# EVB-ANNA-B5_SCHEM_0005_On-Board-Debug.net
KiCad netlist of a schematic drawn in Altium Designer
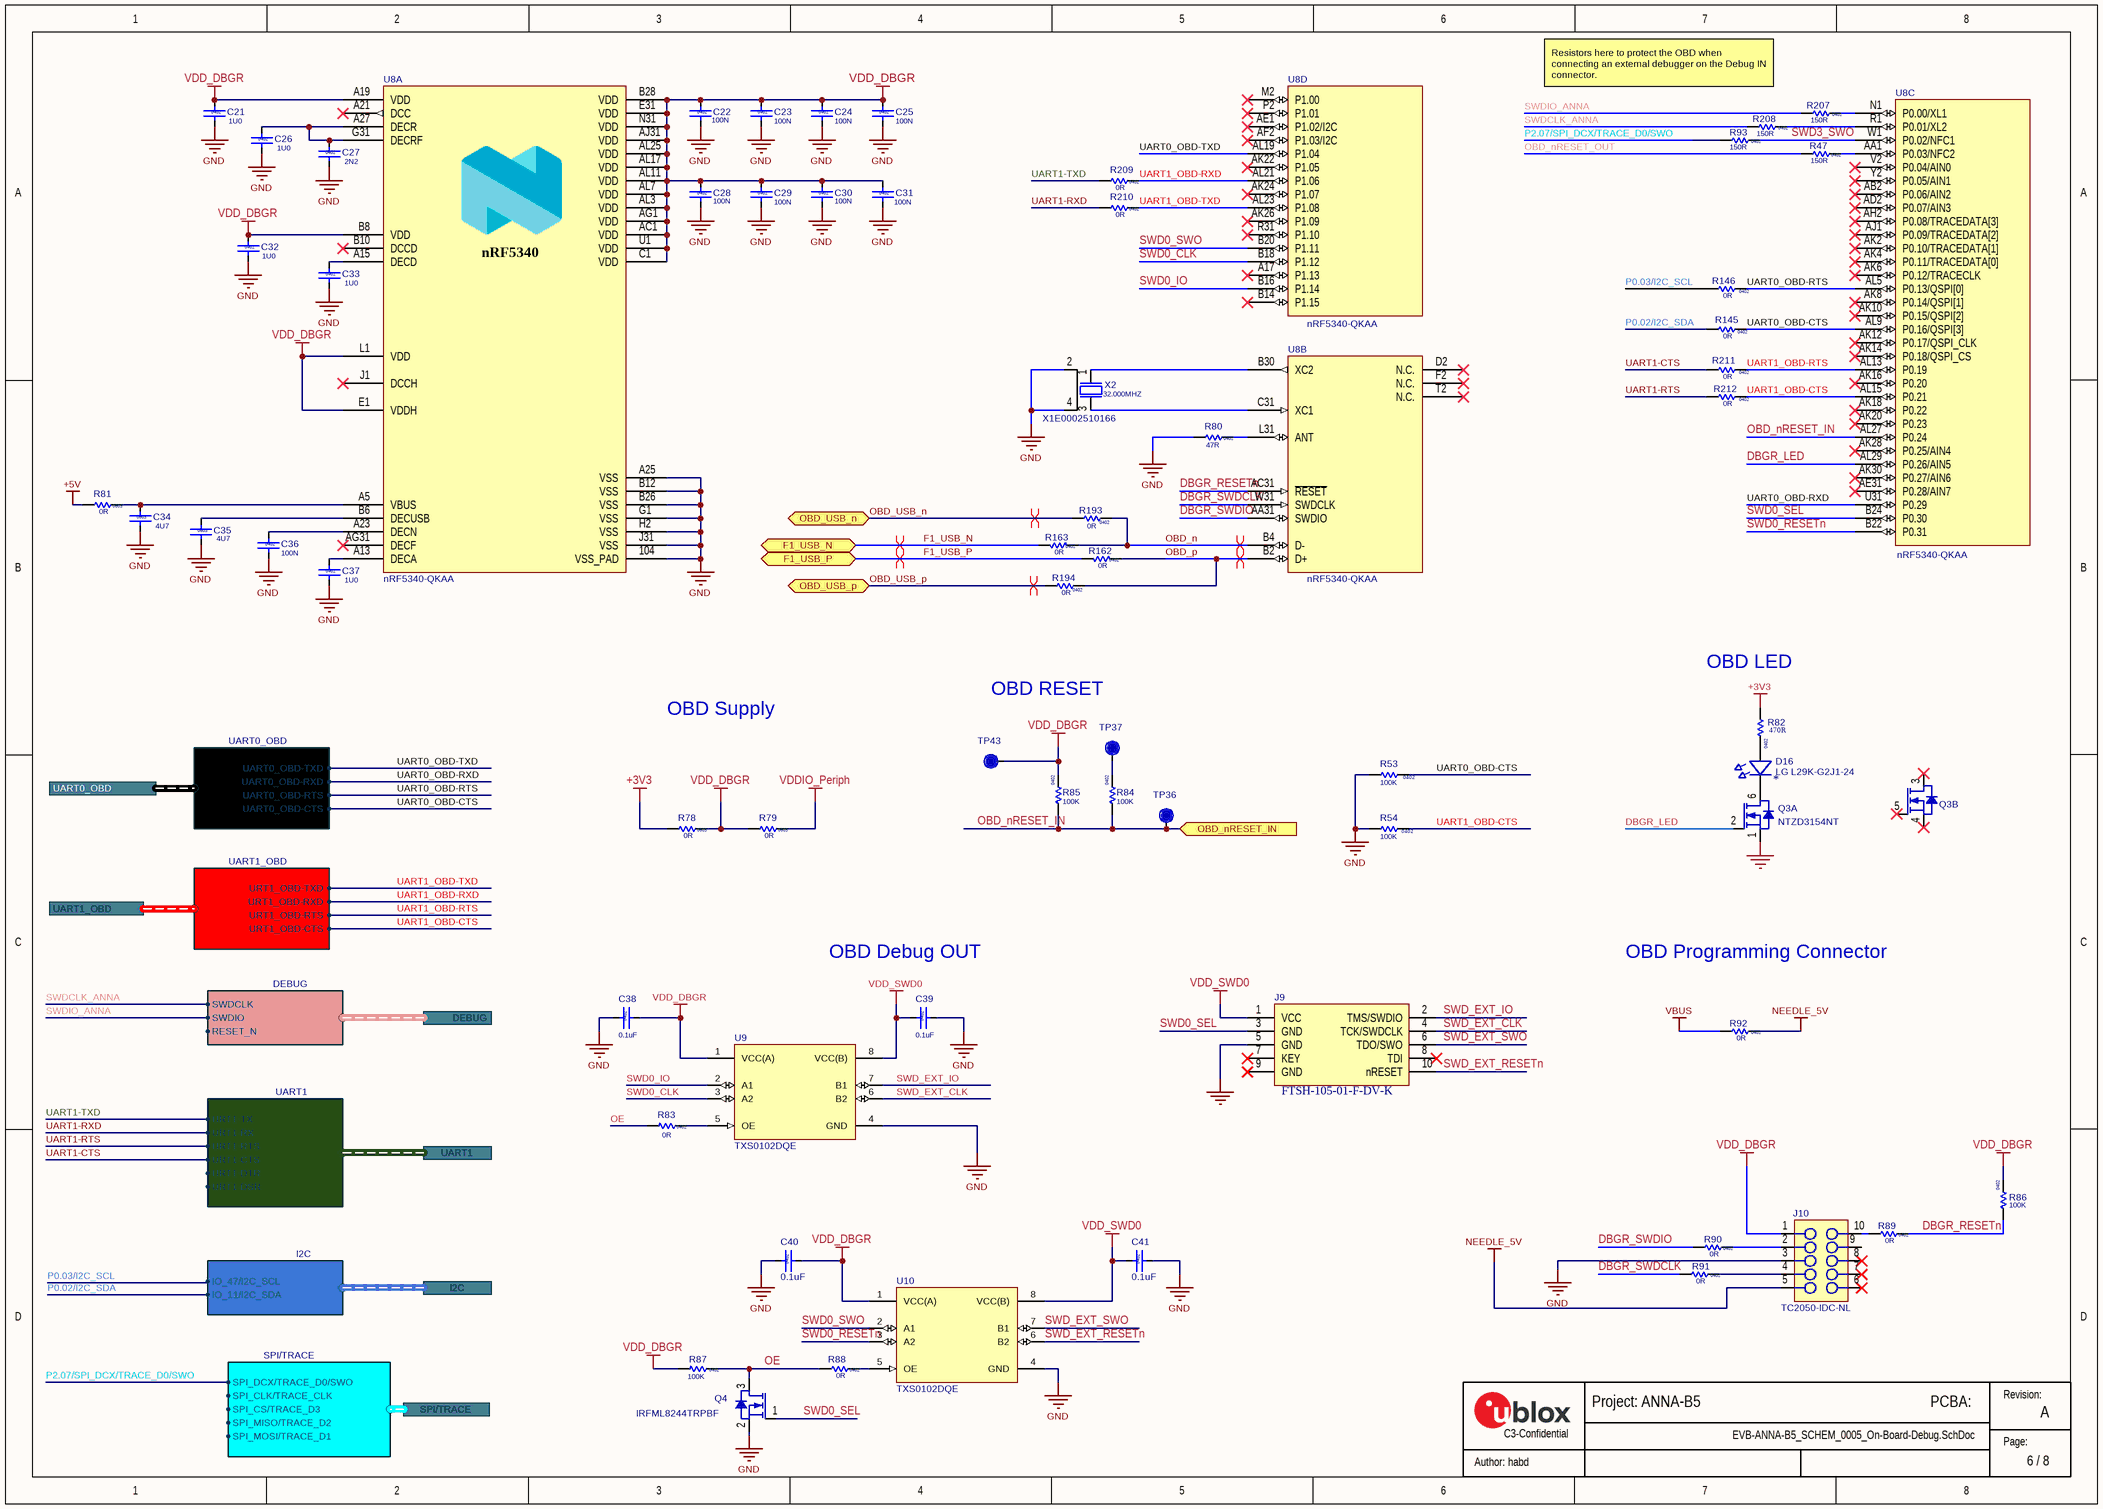
[diagram p0: EVB-ANNA-B5_SCHEM_0005_On-Board-Debug.SchDoc]

(export (version "E")
  (design (tool "Eeschema 10.0.6"))
  (components
    (comp (ref "C21")
      (value "1U0")
      (footprint "Cap_0402_1100Lx600Wx600H_600x600Pad_350G_FLX")
      (description "CAP CER X5R 0402 1U0 10% 6.3V")
      (fields
        (field (name "SIZE") "0402")
        (field (name "PART NUMBER") "UBXH01-2021003")
        (field (name "TOLERANCE") "10%")
      )
      (libsource (lib "UBX_Parts_DB_Lib") (part "Cap Chip"))
    )
    (comp (ref "C22")
      (value "100N")
      (footprint "Cap 0402 HD")
      (description "CAP CER X5R 0402 100N 10% 10V")
      (fields
        (field (name "SIZE") "0402")
        (field (name "PART NUMBER") "UBXH01-2021002")
        (field (name "TOLERANCE") "10%")
      )
      (libsource (lib "UBX_Parts_DB_Lib") (part "Cap Chip"))
    )
    (comp (ref "C23")
      (value "100N")
      (footprint "Cap 0402 HD")
      (description "CAP CER X5R 0402 100N 10% 10V")
      (fields
        (field (name "SIZE") "0402")
        (field (name "PART NUMBER") "UBXH01-2021002")
        (field (name "TOLERANCE") "10%")
      )
      (libsource (lib "UBX_Parts_DB_Lib") (part "Cap Chip"))
    )
    (comp (ref "C24")
      (value "100N")
      (footprint "Cap 0402 HD")
      (description "CAP CER X5R 0402 100N 10% 10V")
      (fields
        (field (name "SIZE") "0402")
        (field (name "PART NUMBER") "UBXH01-2021002")
        (field (name "TOLERANCE") "10%")
      )
      (libsource (lib "UBX_Parts_DB_Lib") (part "Cap Chip"))
    )
    (comp (ref "C25")
      (value "100N")
      (footprint "Cap 0402 HD")
      (description "CAP CER X5R 0402 100N 10% 10V")
      (fields
        (field (name "SIZE") "0402")
        (field (name "PART NUMBER") "UBXH01-2021002")
        (field (name "TOLERANCE") "10%")
      )
      (libsource (lib "UBX_Parts_DB_Lib") (part "Cap Chip"))
    )
    (comp (ref "C26")
      (value "1U0")
      (footprint "Cap_0402_1100Lx600Wx600H_600x600Pad_350G_FLX")
      (description "CAP CER X5R 0402 1U0 10% 6.3V")
      (fields
        (field (name "SIZE") "0402")
        (field (name "PART NUMBER") "UBXH01-2021003")
        (field (name "TOLERANCE") "10%")
      )
      (libsource (lib "UBX_Parts_DB_Lib") (part "Cap Chip"))
    )
    (comp (ref "C27")
      (value "2N2")
      (footprint "Cap_0402_1100Lx600Wx600H_600x600Pad_350G_FLX")
      (description "CAP CER X7R 0402 2N2 10% 16V")
      (fields
        (field (name "SIZE") "0402")
        (field (name "PART NUMBER") "UBXH01-0023017")
        (field (name "TOLERANCE") "10%")
      )
      (libsource (lib "UBX_Parts_DB_Lib") (part "Cap Chip"))
    )
    (comp (ref "C28")
      (value "100N")
      (footprint "Cap 0402 HD")
      (description "CAP CER X5R 0402 100N 10% 10V")
      (fields
        (field (name "SIZE") "0402")
        (field (name "PART NUMBER") "UBXH01-2021002")
        (field (name "TOLERANCE") "10%")
      )
      (libsource (lib "UBX_Parts_DB_Lib") (part "Cap Chip"))
    )
    (comp (ref "C29")
      (value "100N")
      (footprint "Cap 0402 HD")
      (description "CAP CER X5R 0402 100N 10% 10V")
      (fields
        (field (name "SIZE") "0402")
        (field (name "PART NUMBER") "UBXH01-2021002")
        (field (name "TOLERANCE") "10%")
      )
      (libsource (lib "UBX_Parts_DB_Lib") (part "Cap Chip"))
    )
    (comp (ref "C30")
      (value "100N")
      (footprint "Cap 0402 HD")
      (description "CAP CER X5R 0402 100N 10% 10V")
      (fields
        (field (name "SIZE") "0402")
        (field (name "PART NUMBER") "UBXH01-2021002")
        (field (name "TOLERANCE") "10%")
      )
      (libsource (lib "UBX_Parts_DB_Lib") (part "Cap Chip"))
    )
    (comp (ref "C31")
      (value "100N")
      (footprint "Cap 0402 HD")
      (description "CAP CER X5R 0402 100N 10% 10V")
      (fields
        (field (name "SIZE") "0402")
        (field (name "PART NUMBER") "UBXH01-2021002")
        (field (name "TOLERANCE") "10%")
      )
      (libsource (lib "UBX_Parts_DB_Lib") (part "Cap Chip"))
    )
    (comp (ref "C32")
      (value "1U0")
      (footprint "Cap_0402_1100Lx600Wx600H_600x600Pad_350G_FLX")
      (description "CAP CER X5R 0402 1U0 10% 6.3V")
      (fields
        (field (name "SIZE") "0402")
        (field (name "PART NUMBER") "UBXH01-2021003")
        (field (name "TOLERANCE") "10%")
      )
      (libsource (lib "UBX_Parts_DB_Lib") (part "Cap Chip"))
    )
    (comp (ref "C33")
      (value "1U0")
      (footprint "Cap_0402_1100Lx600Wx600H_600x600Pad_350G_FLX")
      (description "CAP CER X5R 0402 1U0 10% 6.3V")
      (fields
        (field (name "SIZE") "0402")
        (field (name "PART NUMBER") "UBXH01-2021003")
        (field (name "TOLERANCE") "10%")
      )
      (libsource (lib "UBX_Parts_DB_Lib") (part "Cap Chip"))
    )
    (comp (ref "C34")
      (value "4U7")
      (footprint "CAP_0603_1750Lx950Wx850H_600x1000Pad_900G_FLX")
      (description "CAP CER X5R 0603 4U7 10% 6.3V")
      (fields
        (field (name "SIZE") "0603")
        (field (name "PART NUMBER") "UBXH01-2002003")
        (field (name "TOLERANCE") "10%")
      )
      (libsource (lib "UBX_Parts_DB_Lib") (part "Cap Chip"))
    )
    (comp (ref "C35")
      (value "4U7")
      (footprint "CAP_0603_1750Lx950Wx850H_600x1000Pad_900G_FLX")
      (description "CAP CER X5R 0603 4U7 10% 6.3V")
      (fields
        (field (name "SIZE") "0603")
        (field (name "PART NUMBER") "UBXH01-2002003")
        (field (name "TOLERANCE") "10%")
      )
      (libsource (lib "UBX_Parts_DB_Lib") (part "Cap Chip"))
    )
    (comp (ref "C36")
      (value "100N")
      (footprint "Cap 0402 HD")
      (description "CAP CER X5R 0402 100N 10% 10V")
      (fields
        (field (name "SIZE") "0402")
        (field (name "PART NUMBER") "UBXH01-2021002")
        (field (name "TOLERANCE") "10%")
      )
      (libsource (lib "UBX_Parts_DB_Lib") (part "Cap Chip"))
    )
    (comp (ref "C37")
      (value "1U0")
      (footprint "Cap_0402_1100Lx600Wx600H_600x600Pad_350G_FLX")
      (description "CAP CER X5R 0402 1U0 10% 6.3V")
      (fields
        (field (name "SIZE") "0402")
        (field (name "PART NUMBER") "UBXH01-2021003")
        (field (name "TOLERANCE") "10%")
      )
      (libsource (lib "UBX_Parts_DB_Lib") (part "Cap Chip"))
    )
    (comp (ref "C38")
      (value "0.1uF")
      (footprint "Cap 0402 HD")
      (description "Cap, Ceramic 0.1uF 10V 10% X5R 0402")
      (fields
        (field (name "SIZE") "0402")
        (field (name "PART NUMBER") "120-00016")
        (field (name "MANUFACTURER") "Murata Electronics North America")
      )
      (libsource (lib "Arena_Parts_DB_Lib") (part "Cap Chip"))
    )
    (comp (ref "C39")
      (value "0.1uF")
      (footprint "Cap 0402 HD")
      (description "Cap, Ceramic 0.1uF 10V 10% X5R 0402")
      (fields
        (field (name "SIZE") "0402")
        (field (name "PART NUMBER") "120-00016")
        (field (name "MANUFACTURER") "Murata Electronics North America")
      )
      (libsource (lib "Arena_Parts_DB_Lib") (part "Cap Chip"))
    )
    (comp (ref "C40")
      (value "0.1uF")
      (footprint "Cap 0402 HD")
      (description "Cap, Ceramic 0.1uF 10V 10% X5R 0402")
      (fields
        (field (name "SIZE") "0402")
        (field (name "PART NUMBER") "120-00016")
        (field (name "MANUFACTURER") "Murata Electronics North America")
      )
      (libsource (lib "Arena_Parts_DB_Lib") (part "Cap Chip"))
    )
    (comp (ref "C41")
      (value "0.1uF")
      (footprint "Cap 0402 HD")
      (description "Cap, Ceramic 0.1uF 10V 10% X5R 0402")
      (fields
        (field (name "SIZE") "0402")
        (field (name "PART NUMBER") "120-00016")
        (field (name "MANUFACTURER") "Murata Electronics North America")
      )
      (libsource (lib "Arena_Parts_DB_Lib") (part "Cap Chip"))
    )
    (comp (ref "D16")
      (value "UBXH11-0000018")
      (footprint "LED_0603_1600Lx800Wx400H_600x800Pad_800G_FLX")
      (description "LED CHIP 0603 LOW CURRENT OSRAM 0.002A GREEN 2.2V 2mA")
      (fields
        (field (name "COLOR") "*")
        (field (name "MANUFACTURER") "Osram")
        (field (name "MANUFACTURER P/N") "LG L29K-G2J1-24")
      )
      (libsource (lib "UBX_Parts_DB_Lib") (part "LED_BASE"))
    )
    (comp (ref "J9")
      (value "130-00099")
      (footprint "HDR.050P-10Pin-2x5-SMT_Key")
      (description "Header 0.05\" 10Pin 2Row SMD Black")
      (fields (field (name "MANUFACTURER") "Samtec") (field (name "MANUFACTURER P/N") "FTSH-105-01-F-DV-K"))
      (libsource (lib "Arena_Parts_DB_Lib") (part "JTAG-10Pin"))
    )
    (comp (ref "J10")
      (value "TC2050-IDC-NL")
      (footprint "TC2050-IDC-NL")
      (description "CON PADS FOR CBL PLUG-OF-NAILS 10-PIN NO LEGS")
      (fields (field (name "MANUFACTURER P/N") "TC2050-IDC-NL") (field (name "MANUFACTURER") "TAG Connect"))
      (libsource (lib "LEGACY_Rigado_AltiumLib") (part "CON-10Pin_2Row_ALT"))
    )
    (comp (ref "Q3")
      (value "NTZD3154NT")
      (footprint "SOT-563")
      (description "DUAL N-CHANNEL SMALL SIGNAL MOSFET SOT-563-6 PACKAGE")
      (fields (field (name "PART NUMBER") "UBXH20-0000083") (field (name "MANUFACTURER") "ON Semiconductor"))
      (libsource (lib "UBX_Parts_DB_Lib") (part "MOSFET-N-Dual"))
    )
    (comp (ref "Q4")
      (value "IRFML8244TRPBF")
      (footprint "SOT-23")
      (description "N-CHANNEL 25V HEXFET SOT23 25V 5.8A")
      (fields
        (field (name "PART NUMBER") "UBXH20-0000036")
        (field (name "MANUFACTURER") "IR International Rectifier")
      )
      (libsource (lib "UBX_Parts_DB_Lib") (part "MOSFET-N"))
    )
    (comp (ref "R47")
      (value "150R")
      (footprint "RES_0402_1100Lx600Wx400H_500x600Pad_400G_FLX")
      (description "RES THICK FILM CHIP 0402 150R 5% 63mW")
      (fields
        (field (name "SIZE") "0402")
        (field (name "PART NUMBER") "UBXH18-0008029")
        (field (name "TOLERANCE") "5%")
      )
      (libsource (lib "UBX_Parts_DB_Lib") (part "Res sm"))
    )
    (comp (ref "R53")
      (value "100K")
      (footprint "RES 0402 HD")
      (description "RES THICK FILM CHIP 0402 100K 1% 63mW")
      (fields
        (field (name "SIZE") "0402")
        (field (name "PART NUMBER") "UBXH18-0000005")
        (field (name "TOLERANCE") "1%")
      )
      (libsource (lib "UBX_Parts_DB_Lib") (part "Res sm"))
    )
    (comp (ref "R54")
      (value "100K")
      (footprint "RES 0402 HD")
      (description "RES THICK FILM CHIP 0402 100K 1% 63mW")
      (fields
        (field (name "SIZE") "0402")
        (field (name "PART NUMBER") "UBXH18-0000005")
        (field (name "TOLERANCE") "1%")
      )
      (libsource (lib "UBX_Parts_DB_Lib") (part "Res sm"))
    )
    (comp (ref "R78")
      (value "0R")
      (footprint "RES_0603_1700Lx950Wx600H_600x1000Pad_800G_FLX")
      (description "RES THICK FILM CHIP 0603 0R 0 100mW")
      (fields
        (field (name "SIZE") "0603")
        (field (name "PART NUMBER") "UBXH18-0003001")
        (field (name "TOLERANCE") "0")
      )
      (libsource (lib "UBX_Parts_DB_Lib") (part "Res sm"))
    )
    (comp (ref "R79")
      (value "0R")
      (footprint "RES_0603_1700Lx950Wx600H_600x1000Pad_800G_FLX")
      (description "RES THICK FILM CHIP 0603 0R 0 100mW")
      (fields
        (field (name "SIZE") "0603")
        (field (name "PART NUMBER") "UBXH18-0003001")
        (field (name "TOLERANCE") "0")
      )
      (libsource (lib "UBX_Parts_DB_Lib") (part "Res sm"))
    )
    (comp (ref "R80")
      (value "47R")
      (footprint "RES_0402_1100Lx600Wx400H_500x600Pad_400G_FLX")
      (description "RES THICK FILM CHIP 0402 47R 5% 100mW")
      (fields
        (field (name "SIZE") "0402")
        (field (name "PART NUMBER") "UBXH18-0008017")
        (field (name "TOLERANCE") "5%")
      )
      (libsource (lib "UBX_Parts_DB_Lib") (part "Res sm"))
    )
    (comp (ref "R81")
      (value "0R")
      (footprint "RES_0603_1700Lx950Wx600H_600x1000Pad_800G_FLX")
      (description "RES THICK FILM CHIP 0603 0R 0 100mW")
      (fields
        (field (name "SIZE") "0603")
        (field (name "PART NUMBER") "UBXH18-0003001")
        (field (name "TOLERANCE") "0")
      )
      (libsource (lib "UBX_Parts_DB_Lib") (part "Res sm"))
    )
    (comp (ref "R82")
      (value "470R")
      (footprint "RES_0402_1100Lx600Wx400H_500x600Pad_400G_FLX")
      (description "RES THICK FILM CHIP 0402 470R 5% 100mW")
      (fields
        (field (name "SIZE") "0402")
        (field (name "PART NUMBER") "UBXH18-0008041")
        (field (name "TOLERANCE") "5%")
      )
      (libsource (lib "UBX_Parts_DB_Lib") (part "Res sm"))
    )
    (comp (ref "R83")
      (value "0R")
      (footprint "RES 0402 HD")
      (description "RES THICK FILM CHIP 0402 0R 0 100mW")
      (fields
        (field (name "SIZE") "0402")
        (field (name "PART NUMBER") "UBXH18-0003002")
        (field (name "TOLERANCE") "0")
      )
      (libsource (lib "UBX_Parts_DB_Lib") (part "Res sm"))
    )
    (comp (ref "R84")
      (value "100K")
      (footprint "RES 0402 HD")
      (description "RES THICK FILM CHIP 0402 100K 1% 63mW")
      (fields
        (field (name "SIZE") "0402")
        (field (name "PART NUMBER") "UBXH18-0000005")
        (field (name "TOLERANCE") "1%")
      )
      (libsource (lib "UBX_Parts_DB_Lib") (part "Res sm"))
    )
    (comp (ref "R85")
      (value "100K")
      (footprint "RES 0402 HD")
      (description "RES THICK FILM CHIP 0402 100K 1% 63mW")
      (fields
        (field (name "SIZE") "0402")
        (field (name "PART NUMBER") "UBXH18-0000005")
        (field (name "TOLERANCE") "1%")
      )
      (libsource (lib "UBX_Parts_DB_Lib") (part "Res sm"))
    )
    (comp (ref "R86")
      (value "100K")
      (footprint "RES 0402 HD")
      (description "RES THICK FILM CHIP 0402 100K 1% 63mW")
      (fields
        (field (name "SIZE") "0402")
        (field (name "PART NUMBER") "UBXH18-0000005")
        (field (name "TOLERANCE") "1%")
      )
      (libsource (lib "UBX_Parts_DB_Lib") (part "Res sm"))
    )
    (comp (ref "R87")
      (value "100K")
      (footprint "RES 0402 HD")
      (description "RES THICK FILM CHIP 0402 100K 1% 63mW")
      (fields
        (field (name "SIZE") "0402")
        (field (name "PART NUMBER") "UBXH18-0000005")
        (field (name "TOLERANCE") "1%")
      )
      (libsource (lib "UBX_Parts_DB_Lib") (part "Res sm"))
    )
    (comp (ref "R88")
      (value "0R")
      (footprint "RES 0402 HD")
      (description "RES THICK FILM CHIP 0402 0R 0 100mW")
      (fields
        (field (name "SIZE") "0402")
        (field (name "PART NUMBER") "UBXH18-0003002")
        (field (name "TOLERANCE") "0")
      )
      (libsource (lib "UBX_Parts_DB_Lib") (part "Res sm"))
    )
    (comp (ref "R89")
      (value "0R")
      (footprint "RES 0402 HD")
      (description "RES THICK FILM CHIP 0402 0R 0 100mW")
      (fields
        (field (name "SIZE") "0402")
        (field (name "PART NUMBER") "UBXH18-0003002")
        (field (name "TOLERANCE") "0")
      )
      (libsource (lib "UBX_Parts_DB_Lib") (part "Res sm"))
    )
    (comp (ref "R90")
      (value "0R")
      (footprint "RES 0402 HD")
      (description "RES THICK FILM CHIP 0402 0R 0 100mW")
      (fields
        (field (name "SIZE") "0402")
        (field (name "PART NUMBER") "UBXH18-0003002")
        (field (name "TOLERANCE") "0")
      )
      (libsource (lib "UBX_Parts_DB_Lib") (part "Res sm"))
    )
    (comp (ref "R91")
      (value "0R")
      (footprint "RES 0402 HD")
      (description "RES THICK FILM CHIP 0402 0R 0 100mW")
      (fields
        (field (name "SIZE") "0402")
        (field (name "PART NUMBER") "UBXH18-0003002")
        (field (name "TOLERANCE") "0")
      )
      (libsource (lib "UBX_Parts_DB_Lib") (part "Res sm"))
    )
    (comp (ref "R92")
      (value "0R")
      (footprint "RES 0402 HD")
      (description "RES THICK FILM CHIP 0402 0R 0 100mW")
      (fields
        (field (name "SIZE") "0402")
        (field (name "PART NUMBER") "UBXH18-0003002")
        (field (name "TOLERANCE") "0")
      )
      (libsource (lib "UBX_Parts_DB_Lib") (part "Res sm"))
    )
    (comp (ref "R93")
      (value "150R")
      (footprint "RES_0402_1100Lx600Wx400H_500x600Pad_400G_FLX")
      (description "RES THICK FILM CHIP 0402 150R 5% 63mW")
      (fields
        (field (name "SIZE") "0402")
        (field (name "PART NUMBER") "UBXH18-0008029")
        (field (name "TOLERANCE") "5%")
      )
      (libsource (lib "UBX_Parts_DB_Lib") (part "Res sm"))
    )
    (comp (ref "R145")
      (value "0R")
      (footprint "RES 0402 HD")
      (description "RES THICK FILM CHIP 0402 0R 0 100mW")
      (fields
        (field (name "SIZE") "0402")
        (field (name "PART NUMBER") "UBXH18-0003002")
        (field (name "TOLERANCE") "0")
      )
      (libsource (lib "UBX_Parts_DB_Lib") (part "Res sm"))
    )
    (comp (ref "R146")
      (value "0R")
      (footprint "RES 0402 HD")
      (description "RES THICK FILM CHIP 0402 0R 0 100mW")
      (fields
        (field (name "SIZE") "0402")
        (field (name "PART NUMBER") "UBXH18-0003002")
        (field (name "TOLERANCE") "0")
      )
      (libsource (lib "UBX_Parts_DB_Lib") (part "Res sm"))
    )
    (comp (ref "R162")
      (value "0R")
      (footprint "RES 0402 HD")
      (description "RES THICK FILM CHIP 0402 0R 0 100mW")
      (fields
        (field (name "SIZE") "0402")
        (field (name "PART NUMBER") "UBXH18-0003002")
        (field (name "TOLERANCE") "0")
      )
      (libsource (lib "UBX_Parts_DB_Lib") (part "Res sm"))
    )
    (comp (ref "R163")
      (value "0R")
      (footprint "RES 0402 HD")
      (description "RES THICK FILM CHIP 0402 0R 0 100mW")
      (fields
        (field (name "SIZE") "0402")
        (field (name "PART NUMBER") "UBXH18-0003002")
        (field (name "TOLERANCE") "0")
      )
      (libsource (lib "UBX_Parts_DB_Lib") (part "Res sm"))
    )
    (comp (ref "R193")
      (value "0R")
      (footprint "RES 0402 HD")
      (description "RES THICK FILM CHIP 0402 0R 0 100mW")
      (fields
        (field (name "SIZE") "0402")
        (field (name "PART NUMBER") "UBXH18-0003002")
        (field (name "TOLERANCE") "0")
      )
      (libsource (lib "UBX_Parts_DB_Lib") (part "Res sm"))
    )
    (comp (ref "R194")
      (value "0R")
      (footprint "RES 0402 HD")
      (description "RES THICK FILM CHIP 0402 0R 0 100mW")
      (fields
        (field (name "SIZE") "0402")
        (field (name "PART NUMBER") "UBXH18-0003002")
        (field (name "TOLERANCE") "0")
      )
      (libsource (lib "UBX_Parts_DB_Lib") (part "Res sm"))
    )
    (comp (ref "R207")
      (value "150R")
      (footprint "RES_0402_1100Lx600Wx400H_500x600Pad_400G_FLX")
      (description "RES THICK FILM CHIP 0402 150R 5% 63mW")
      (fields
        (field (name "SIZE") "0402")
        (field (name "PART NUMBER") "UBXH18-0008029")
        (field (name "TOLERANCE") "5%")
      )
      (libsource (lib "UBX_Parts_DB_Lib") (part "Res sm"))
    )
    (comp (ref "R208")
      (value "150R")
      (footprint "RES_0402_1100Lx600Wx400H_500x600Pad_400G_FLX")
      (description "RES THICK FILM CHIP 0402 150R 5% 63mW")
      (fields
        (field (name "SIZE") "0402")
        (field (name "PART NUMBER") "UBXH18-0008029")
        (field (name "TOLERANCE") "5%")
      )
      (libsource (lib "UBX_Parts_DB_Lib") (part "Res sm"))
    )
    (comp (ref "R209")
      (value "0R")
      (footprint "RES 0402 HD")
      (description "RES THICK FILM CHIP 0402 0R 0 100mW")
      (fields
        (field (name "SIZE") "0402")
        (field (name "PART NUMBER") "UBXH18-0003002")
        (field (name "TOLERANCE") "0")
      )
      (libsource (lib "UBX_Parts_DB_Lib") (part "Res sm"))
    )
    (comp (ref "R210")
      (value "0R")
      (footprint "RES 0402 HD")
      (description "RES THICK FILM CHIP 0402 0R 0 100mW")
      (fields
        (field (name "SIZE") "0402")
        (field (name "PART NUMBER") "UBXH18-0003002")
        (field (name "TOLERANCE") "0")
      )
      (libsource (lib "UBX_Parts_DB_Lib") (part "Res sm"))
    )
    (comp (ref "R211")
      (value "0R")
      (footprint "RES 0402 HD")
      (description "RES THICK FILM CHIP 0402 0R 0 100mW")
      (fields
        (field (name "SIZE") "0402")
        (field (name "PART NUMBER") "UBXH18-0003002")
        (field (name "TOLERANCE") "0")
      )
      (libsource (lib "UBX_Parts_DB_Lib") (part "Res sm"))
    )
    (comp (ref "R212")
      (value "0R")
      (footprint "RES 0402 HD")
      (description "RES THICK FILM CHIP 0402 0R 0 100mW")
      (fields
        (field (name "SIZE") "0402")
        (field (name "PART NUMBER") "UBXH18-0003002")
        (field (name "TOLERANCE") "0")
      )
      (libsource (lib "UBX_Parts_DB_Lib") (part "Res sm"))
    )
    (comp (ref "TP36")
      (value "TP10R")
      (footprint "TP10R")
      (description "Testpoint, Round 1.0mm Dia")
      (libsource (lib "LEGACY_Rigado_AltiumLib") (part "TP_R"))
    )
    (comp (ref "TP37")
      (value "TP10R")
      (footprint "TP10R")
      (description "Testpoint, Round 1.0mm Dia")
      (libsource (lib "LEGACY_Rigado_AltiumLib") (part "TP_R"))
    )
    (comp (ref "TP43")
      (value "TP10R")
      (footprint "TP10R")
      (description "Testpoint, Round 1.0mm Dia")
      (libsource (lib "LEGACY_Rigado_AltiumLib") (part "TP_R"))
    )
    (comp (ref "U8")
      (value "UBXH12-0000420")
      (footprint "nRF5340_AQFN94")
      (description "BT5/802.15.4 SOC NORDIC NRF5340 2.4GHZ")
      (fields
        (field (name "MANUFACTURER P/N") "nRF5340-QKAA")
        (field (name "MANUFACTURER") "Nordic Semiconductor")
      )
      (libsource (lib "UBX_Parts_DB_Lib") (part "nRF5340_qkaa"))
    )
    (comp (ref "U9")
      (value "TXS0102DQE")
      (footprint "DQE0008A")
      (description "TXS0102 2-BIT BIDIRECTIONAL VOLTAGE-LEVEL TRANSLATOR X2SON-8 TXS0102DQE 5.5V")
      (fields (field (name "PART NUMBER") "UBXH10-0000108") (field (name "MANUFACTURER") "Texas Instruments"))
      (libsource (lib "UBX_Parts_DB_Lib") (part "TXS0102DQE"))
    )
    (comp (ref "U10")
      (value "TXS0102DQE")
      (footprint "DQE0008A")
      (description "TXS0102 2-BIT BIDIRECTIONAL VOLTAGE-LEVEL TRANSLATOR X2SON-8 TXS0102DQE 5.5V")
      (fields (field (name "PART NUMBER") "UBXH10-0000108") (field (name "MANUFACTURER") "Texas Instruments"))
      (libsource (lib "UBX_Parts_DB_Lib") (part "TXS0102DQE"))
    )
    (comp (ref "X2")
      (value "32.000MHZ")
      (footprint "XTAL_1612")
      (description "CRYSTAL 32MHZ CL=8PF 1.6X1.2 MM 32.000MHZ +/-10PPM@25C+/-20PPM@-40/+85+/-1PPMAGEING")
      (fields
        (field (name "PART NUMBER") "UBXH21-0000240")
        (field (name "TOLERANCE") "+/-10PPM@25C+/-20PPM@-40/+85+/-1PPMAGEING")
        (field (name "MANUFACTURER P/N") "X1E0002510166")
      )
      (libsource (lib "UBX_Parts_DB_Lib") (part "XTAL_4Pin"))
    )
  )
  (nets
    (net (code "7") (name "+3V3") (class "Default")
      (node (ref "R78") (pin "1") (pinfunction "1_1") (pintype "passive"))
      (node (ref "R82") (pin "1") (pinfunction "1_1") (pintype "passive"))
    )
    (net (code "8") (name "+5V") (class "Default")
      (node (ref "R81") (pin "1") (pinfunction "1_1") (pintype "passive"))
    )
    (net (code "9") (name "/DBGR_LED") (class "Default")
      (node (ref "Q3") (pin "2") (pinfunction "G1_2") (pintype "passive"))
      (node (ref "U8") (pin "AL29") (pinfunction "P0.26/AIN5_AL29") (pintype "bidirectional"))
    )
    (net (code "10") (name "/DBGR_RESETn") (class "Default")
      (node (ref "R86") (pin "1") (pinfunction "1_1") (pintype "passive"))
      (node (ref "R89") (pin "1") (pinfunction "1_1") (pintype "passive"))
      (node (ref "U8") (pin "AC31") (pinfunction "~{RESET}_AC31") (pintype "input"))
    )
    (net (code "11") (name "/DBGR_SWDCLK") (class "Default")
      (node (ref "R91") (pin "2") (pinfunction "2_2") (pintype "passive"))
      (node (ref "U8") (pin "W31") (pinfunction "SWDCLK_W31") (pintype "input"))
    )
    (net (code "12") (name "/DBGR_SWDIO") (class "Default")
      (node (ref "R90") (pin "2") (pinfunction "2_2") (pintype "passive"))
      (node (ref "U8") (pin "AA31") (pinfunction "SWDIO_AA31") (pintype "bidirectional"))
    )
    (net (code "13") (name "/F1_USB_N") (class "Default")
      (node (ref "R163") (pin "2") (pinfunction "2_2") (pintype "passive"))
    )
    (net (code "14") (name "/F1_USB_P") (class "Default")
      (node (ref "R162") (pin "2") (pinfunction "2_2") (pintype "passive"))
    )
    (net (code "15") (name "/OBD_USB_n") (class "Default")
      (node (ref "R193") (pin "2") (pinfunction "2_2") (pintype "passive"))
    )
    (net (code "16") (name "/OBD_USB_p") (class "Default")
      (node (ref "R194") (pin "2") (pinfunction "2_2") (pintype "passive"))
    )
    (net (code "17") (name "/OBD_n") (class "Default")
      (node (ref "R163") (pin "1") (pinfunction "1_1") (pintype "passive"))
      (node (ref "R193") (pin "1") (pinfunction "1_1") (pintype "passive"))
      (node (ref "U8") (pin "B4") (pinfunction "D-_B4") (pintype "bidirectional"))
    )
    (net (code "18") (name "/OBD_nRESET_IN") (class "Default")
      (node (ref "R84") (pin "1") (pinfunction "1_1") (pintype "passive"))
      (node (ref "R85") (pin "1") (pinfunction "1_1") (pintype "passive"))
      (node (ref "TP36") (pin "1") (pintype "passive"))
      (node (ref "U8") (pin "AL27") (pinfunction "P0.24_AL27") (pintype "bidirectional"))
    )
    (net (code "19") (name "/OBD_nRESET_OUT") (class "Default")
      (node (ref "R47") (pin "1") (pinfunction "1_1") (pintype "passive"))
    )
    (net (code "20") (name "/OBD_p") (class "Default")
      (node (ref "R162") (pin "1") (pinfunction "1_1") (pintype "passive"))
      (node (ref "R194") (pin "1") (pinfunction "1_1") (pintype "passive"))
      (node (ref "U8") (pin "B2") (pinfunction "D+_B2") (pintype "bidirectional"))
    )
    (net (code "21") (name "/OE") (class "Default")
      (node (ref "Q4") (pin "3") (pinfunction "D_3") (pintype "passive"))
      (node (ref "R83") (pin "2") (pinfunction "2_2") (pintype "passive"))
      (node (ref "R87") (pin "1") (pinfunction "1_1") (pintype "passive"))
      (node (ref "R88") (pin "1") (pinfunction "1_1") (pintype "passive"))
    )
    (net (code "22") (name "/P0.02{slash}I2C_SDA") (class "Default")
      (node (ref "R145") (pin "2") (pinfunction "2_2") (pintype "passive"))
    )
    (net (code "23") (name "/P0.03{slash}I2C_SCL") (class "Default")
      (node (ref "R146") (pin "2") (pinfunction "2_2") (pintype "passive"))
    )
    (net (code "24") (name "/P2.07{slash}SPI_DCX{slash}TRACE_D0{slash}SWO") (class "Default")
      (node (ref "R93") (pin "1") (pinfunction "1_1") (pintype "passive"))
    )
    (net (code "25") (name "/SWD0_CLK") (class "Default")
      (node (ref "U8") (pin "B18") (pinfunction "P1.12_B18") (pintype "bidirectional"))
      (node (ref "U9") (pin "3") (pinfunction "A2_3") (pintype "bidirectional"))
    )
    (net (code "26") (name "/SWD0_IO") (class "Default")
      (node (ref "U8") (pin "B16") (pinfunction "P1.14_B16") (pintype "bidirectional"))
      (node (ref "U9") (pin "2") (pinfunction "A1_2") (pintype "bidirectional"))
    )
    (net (code "27") (name "/SWD0_RESETn") (class "Default")
      (node (ref "U10") (pin "3") (pinfunction "A2_3") (pintype "bidirectional"))
      (node (ref "U8") (pin "B22") (pinfunction "P0.31_B22") (pintype "bidirectional"))
    )
    (net (code "28") (name "/SWD0_SEL") (class "Default")
      (node (ref "J9") (pin "3") (pinfunction "GND_3") (pintype "passive"))
      (node (ref "Q4") (pin "1") (pinfunction "G_1") (pintype "passive"))
      (node (ref "U8") (pin "B24") (pinfunction "P0.30_B24") (pintype "bidirectional"))
    )
    (net (code "29") (name "/SWD0_SWO") (class "Default")
      (node (ref "U10") (pin "2") (pinfunction "A1_2") (pintype "bidirectional"))
      (node (ref "U8") (pin "B20") (pinfunction "P1.11_B20") (pintype "bidirectional"))
    )
    (net (code "30") (name "/SWD3_SWO") (class "Default")
      (node (ref "R93") (pin "2") (pinfunction "2_2") (pintype "passive"))
      (node (ref "U8") (pin "W1") (pinfunction "P0.02/NFC1_W1") (pintype "bidirectional"))
    )
    (net (code "31") (name "/SWDCLK_ANNA") (class "Default")
      (node (ref "R208") (pin "1") (pinfunction "1_1") (pintype "passive"))
    )
    (net (code "32") (name "/SWDIO_ANNA") (class "Default")
      (node (ref "R207") (pin "1") (pinfunction "1_1") (pintype "passive"))
    )
    (net (code "33") (name "/SWD_EXT_CLK") (class "Default")
      (node (ref "J9") (pin "4") (pinfunction "TCK/SWDCLK_4") (pintype "passive"))
      (node (ref "U9") (pin "6") (pinfunction "B2_6") (pintype "bidirectional"))
    )
    (net (code "34") (name "/SWD_EXT_IO") (class "Default")
      (node (ref "J9") (pin "2") (pinfunction "TMS/SWDIO_2") (pintype "passive"))
      (node (ref "U9") (pin "7") (pinfunction "B1_7") (pintype "bidirectional"))
    )
    (net (code "35") (name "/SWD_EXT_RESETn") (class "Default")
      (node (ref "J9") (pin "10") (pinfunction "nRESET_10") (pintype "passive"))
      (node (ref "U10") (pin "6") (pinfunction "B2_6") (pintype "bidirectional"))
    )
    (net (code "36") (name "/SWD_EXT_SWO") (class "Default")
      (node (ref "J9") (pin "6") (pinfunction "TDO/SWO_6") (pintype "passive"))
      (node (ref "U10") (pin "7") (pinfunction "B1_7") (pintype "bidirectional"))
    )
    (net (code "37") (name "/UART0_OBD-CTS") (class "Default")
      (node (ref "R145") (pin "1") (pinfunction "1_1") (pintype "passive"))
      (node (ref "R53") (pin "2") (pinfunction "2_2") (pintype "passive"))
      (node (ref "U8") (pin "AL9") (pinfunction "P0.16/QSPI[3]_AL9") (pintype "bidirectional"))
    )
    (net (code "38") (name "/UART0_OBD-RTS") (class "Default")
      (node (ref "R146") (pin "1") (pinfunction "1_1") (pintype "passive"))
      (node (ref "U8") (pin "AL5") (pinfunction "P0.13/QSPI[0]_AL5") (pintype "bidirectional"))
    )
    (net (code "39") (name "/UART0_OBD-RXD") (class "Default")
      (node (ref "U8") (pin "U31") (pinfunction "P0.29_U31") (pintype "bidirectional"))
    )
    (net (code "40") (name "/UART0_OBD-TXD") (class "Default")
      (node (ref "U8") (pin "AL19") (pinfunction "P1.04_AL19") (pintype "bidirectional"))
    )
    (net (code "41") (name "/UART1-CTS") (class "Default")
      (node (ref "R211") (pin "2") (pinfunction "2_2") (pintype "passive"))
    )
    (net (code "42") (name "/UART1-RTS") (class "Default")
      (node (ref "R212") (pin "2") (pinfunction "2_2") (pintype "passive"))
    )
    (net (code "43") (name "/UART1-RXD") (class "Default")
      (node (ref "R210") (pin "2") (pinfunction "2_2") (pintype "passive"))
    )
    (net (code "44") (name "/UART1-TXD") (class "Default")
      (node (ref "R209") (pin "2") (pinfunction "2_2") (pintype "passive"))
    )
    (net (code "45") (name "/UART1_OBD-CTS") (class "Default")
      (node (ref "R212") (pin "1") (pinfunction "1_1") (pintype "passive"))
      (node (ref "R54") (pin "2") (pinfunction "2_2") (pintype "passive"))
      (node (ref "U8") (pin "AL15") (pinfunction "P0.21_AL15") (pintype "bidirectional"))
    )
    (net (code "46") (name "/UART1_OBD-RTS") (class "Default")
      (node (ref "R211") (pin "1") (pinfunction "1_1") (pintype "passive"))
      (node (ref "U8") (pin "AL13") (pinfunction "P0.19_AL13") (pintype "bidirectional"))
    )
    (net (code "47") (name "/UART1_OBD-RXD") (class "Default")
      (node (ref "R209") (pin "1") (pinfunction "1_1") (pintype "passive"))
      (node (ref "U8") (pin "AL21") (pinfunction "P1.06_AL21") (pintype "bidirectional"))
    )
    (net (code "48") (name "/UART1_OBD-TXD") (class "Default")
      (node (ref "R210") (pin "1") (pinfunction "1_1") (pintype "passive"))
      (node (ref "U8") (pin "AL23") (pinfunction "P1.08_AL23") (pintype "bidirectional"))
    )
    (net (code "55") (name "GND") (class "Default")
      (node (ref "C21") (pin "2") (pinfunction "2_2") (pintype "passive"))
      (node (ref "C22") (pin "2") (pinfunction "2_2") (pintype "passive"))
      (node (ref "C23") (pin "2") (pinfunction "2_2") (pintype "passive"))
      (node (ref "C24") (pin "2") (pinfunction "2_2") (pintype "passive"))
      (node (ref "C25") (pin "2") (pinfunction "2_2") (pintype "passive"))
      (node (ref "C26") (pin "2") (pinfunction "2_2") (pintype "passive"))
      (node (ref "C27") (pin "2") (pinfunction "2_2") (pintype "passive"))
      (node (ref "C28") (pin "2") (pinfunction "2_2") (pintype "passive"))
      (node (ref "C29") (pin "2") (pinfunction "2_2") (pintype "passive"))
      (node (ref "C30") (pin "2") (pinfunction "2_2") (pintype "passive"))
      (node (ref "C31") (pin "2") (pinfunction "2_2") (pintype "passive"))
      (node (ref "C32") (pin "2") (pinfunction "2_2") (pintype "passive"))
      (node (ref "C33") (pin "2") (pinfunction "2_2") (pintype "passive"))
      (node (ref "C34") (pin "2") (pinfunction "2_2") (pintype "passive"))
      (node (ref "C35") (pin "2") (pinfunction "2_2") (pintype "passive"))
      (node (ref "C36") (pin "2") (pinfunction "2_2") (pintype "passive"))
      (node (ref "C37") (pin "2") (pinfunction "2_2") (pintype "passive"))
      (node (ref "C38") (pin "1") (pinfunction "1_1") (pintype "passive"))
      (node (ref "C39") (pin "2") (pinfunction "2_2") (pintype "passive"))
      (node (ref "C40") (pin "1") (pinfunction "1_1") (pintype "passive"))
      (node (ref "C41") (pin "2") (pinfunction "2_2") (pintype "passive"))
      (node (ref "J10") (pin "3") (pintype "passive"))
      (node (ref "J9") (pin "5") (pinfunction "GND_5") (pintype "passive"))
      (node (ref "Q3") (pin "1") (pinfunction "S1_1") (pintype "passive"))
      (node (ref "Q4") (pin "2") (pinfunction "S_2") (pintype "passive"))
      (node (ref "R53") (pin "1") (pinfunction "1_1") (pintype "passive"))
      (node (ref "R54") (pin "1") (pinfunction "1_1") (pintype "passive"))
      (node (ref "R80") (pin "1") (pinfunction "1_1") (pintype "passive"))
      (node (ref "U10") (pin "4") (pinfunction "GND_4") (pintype "power_in"))
      (node (ref "U8") (pin "104") (pinfunction "VSS_PAD_104") (pintype "power_in"))
      (node (ref "U8") (pin "A25") (pinfunction "VSS_A25") (pintype "power_in"))
      (node (ref "U8") (pin "B12") (pinfunction "VSS_B12") (pintype "power_in"))
      (node (ref "U8") (pin "B26") (pinfunction "VSS_B26") (pintype "power_in"))
      (node (ref "U8") (pin "G1") (pinfunction "VSS_G1") (pintype "power_in"))
      (node (ref "U8") (pin "H2") (pinfunction "VSS_H2") (pintype "power_in"))
      (node (ref "U8") (pin "J31") (pinfunction "VSS_J31") (pintype "power_in"))
      (node (ref "U9") (pin "4") (pinfunction "GND_4") (pintype "power_in"))
      (node (ref "X2") (pin "2") (pintype "passive"))
      (node (ref "X2") (pin "4") (pintype "passive"))
    )
    (net (code "56") (name "NEEDLE_5V") (class "Default")
      (node (ref "J10") (pin "5") (pintype "passive"))
      (node (ref "R92") (pin "1") (pinfunction "1_1") (pintype "passive"))
    )
    (net (code "57") (name "Net-(D16-A)") (class "Default")
      (node (ref "D16") (pin "2") (pinfunction "A_2") (pintype "passive"))
      (node (ref "R82") (pin "2") (pinfunction "2_2") (pintype "passive"))
    )
    (net (code "58") (name "Net-(D16-C)") (class "Default")
      (node (ref "D16") (pin "1") (pinfunction "C_1") (pintype "passive"))
      (node (ref "Q3") (pin "6") (pinfunction "D1_6") (pintype "passive"))
    )
    (net (code "59") (name "Net-(J10-Pad2)") (class "Default")
      (node (ref "J10") (pin "2") (pintype "passive"))
      (node (ref "R90") (pin "1") (pinfunction "1_1") (pintype "passive"))
    )
    (net (code "60") (name "Net-(J10-Pad4)") (class "Default")
      (node (ref "J10") (pin "4") (pintype "passive"))
      (node (ref "R91") (pin "1") (pinfunction "1_1") (pintype "passive"))
    )
    (net (code "61") (name "Net-(J10-Pad10)") (class "Default")
      (node (ref "J10") (pin "10") (pintype "passive"))
      (node (ref "R89") (pin "2") (pinfunction "2_2") (pintype "passive"))
    )
    (net (code "62") (name "Net-(R84-Pad2)") (class "Default")
      (node (ref "R84") (pin "2") (pinfunction "2_2") (pintype "passive"))
      (node (ref "TP37") (pin "1") (pintype "passive"))
    )
    (net (code "63") (name "Net-(U8A-DECA)") (class "Default")
      (node (ref "C37") (pin "1") (pinfunction "1_1") (pintype "passive"))
      (node (ref "U8") (pin "A13") (pinfunction "DECA_A13") (pintype "power_in"))
    )
    (net (code "64") (name "Net-(U8A-DECD)") (class "Default")
      (node (ref "C33") (pin "1") (pinfunction "1_1") (pintype "passive"))
      (node (ref "U8") (pin "A15") (pinfunction "DECD_A15") (pintype "power_in"))
    )
    (net (code "65") (name "Net-(U8A-DECN)") (class "Default")
      (node (ref "C36") (pin "1") (pinfunction "1_1") (pintype "passive"))
      (node (ref "U8") (pin "A23") (pinfunction "DECN_A23") (pintype "power_in"))
    )
    (net (code "66") (name "Net-(U8A-DECR)") (class "Default")
      (node (ref "C26") (pin "1") (pinfunction "1_1") (pintype "passive"))
      (node (ref "C27") (pin "1") (pinfunction "1_1") (pintype "passive"))
      (node (ref "U8") (pin "A27") (pinfunction "DECR_A27") (pintype "power_in"))
      (node (ref "U8") (pin "G31") (pinfunction "DECRF_G31") (pintype "power_in"))
    )
    (net (code "67") (name "Net-(U8A-DECUSB)") (class "Default")
      (node (ref "C35") (pin "1") (pinfunction "1_1") (pintype "passive"))
      (node (ref "U8") (pin "B6") (pinfunction "DECUSB_B6") (pintype "power_in"))
    )
    (net (code "68") (name "Net-(U8A-VBUS)") (class "Default")
      (node (ref "C34") (pin "1") (pinfunction "1_1") (pintype "passive"))
      (node (ref "R81") (pin "2") (pinfunction "2_2") (pintype "passive"))
      (node (ref "U8") (pin "A5") (pinfunction "VBUS_A5") (pintype "power_in"))
    )
    (net (code "69") (name "Net-(U8B-ANT)") (class "Default")
      (node (ref "R80") (pin "2") (pinfunction "2_2") (pintype "passive"))
      (node (ref "U8") (pin "L31") (pinfunction "ANT_L31") (pintype "bidirectional"))
    )
    (net (code "70") (name "Net-(U8B-XC1)") (class "Default")
      (node (ref "U8") (pin "C31") (pinfunction "XC1_C31") (pintype "input"))
      (node (ref "X2") (pin "3") (pintype "passive"))
    )
    (net (code "71") (name "Net-(U8B-XC2)") (class "Default")
      (node (ref "U8") (pin "B30") (pinfunction "XC2_B30") (pintype "output"))
      (node (ref "X2") (pin "1") (pintype "passive"))
    )
    (net (code "72") (name "Net-(U8C-P0.00{slash}XL1)") (class "Default")
      (node (ref "R207") (pin "2") (pinfunction "2_2") (pintype "passive"))
      (node (ref "U8") (pin "N1") (pinfunction "P0.00/XL1_N1") (pintype "bidirectional"))
    )
    (net (code "73") (name "Net-(U8C-P0.01{slash}XL2)") (class "Default")
      (node (ref "R208") (pin "2") (pinfunction "2_2") (pintype "passive"))
      (node (ref "U8") (pin "R1") (pinfunction "P0.01/XL2_R1") (pintype "bidirectional"))
    )
    (net (code "74") (name "Net-(U8C-P0.03{slash}NFC2)") (class "Default")
      (node (ref "R47") (pin "2") (pinfunction "2_2") (pintype "passive"))
      (node (ref "U8") (pin "AA1") (pinfunction "P0.03/NFC2_AA1") (pintype "bidirectional"))
    )
    (net (code "75") (name "Net-(U9-OE)") (class "Default")
      (node (ref "R83") (pin "1") (pinfunction "1_1") (pintype "passive"))
      (node (ref "U9") (pin "5") (pinfunction "OE_5") (pintype "input"))
    )
    (net (code "76") (name "Net-(U10-OE)") (class "Default")
      (node (ref "R88") (pin "2") (pinfunction "2_2") (pintype "passive"))
      (node (ref "U10") (pin "5") (pinfunction "OE_5") (pintype "input"))
    )
    (net (code "77") (name "VBUS") (class "Default")
      (node (ref "R92") (pin "2") (pinfunction "2_2") (pintype "passive"))
    )
    (net (code "78") (name "VDDIO_Periph") (class "Default")
      (node (ref "R79") (pin "2") (pinfunction "2_2") (pintype "passive"))
    )
    (net (code "79") (name "VDD_DBGR") (class "Default")
      (node (ref "C21") (pin "1") (pinfunction "1_1") (pintype "passive"))
      (node (ref "C22") (pin "1") (pinfunction "1_1") (pintype "passive"))
      (node (ref "C23") (pin "1") (pinfunction "1_1") (pintype "passive"))
      (node (ref "C24") (pin "1") (pinfunction "1_1") (pintype "passive"))
      (node (ref "C25") (pin "1") (pinfunction "1_1") (pintype "passive"))
      (node (ref "C28") (pin "1") (pinfunction "1_1") (pintype "passive"))
      (node (ref "C29") (pin "1") (pinfunction "1_1") (pintype "passive"))
      (node (ref "C30") (pin "1") (pinfunction "1_1") (pintype "passive"))
      (node (ref "C31") (pin "1") (pinfunction "1_1") (pintype "passive"))
      (node (ref "C32") (pin "1") (pinfunction "1_1") (pintype "passive"))
      (node (ref "C38") (pin "2") (pinfunction "2_2") (pintype "passive"))
      (node (ref "C40") (pin "2") (pinfunction "2_2") (pintype "passive"))
      (node (ref "J10") (pin "1") (pintype "passive"))
      (node (ref "R78") (pin "2") (pinfunction "2_2") (pintype "passive"))
      (node (ref "R79") (pin "1") (pinfunction "1_1") (pintype "passive"))
      (node (ref "R85") (pin "2") (pinfunction "2_2") (pintype "passive"))
      (node (ref "R86") (pin "2") (pinfunction "2_2") (pintype "passive"))
      (node (ref "R87") (pin "2") (pinfunction "2_2") (pintype "passive"))
      (node (ref "TP43") (pin "1") (pintype "passive"))
      (node (ref "U10") (pin "1") (pinfunction "VCC(A)_1") (pintype "power_in"))
      (node (ref "U8") (pin "A19") (pinfunction "VDD_A19") (pintype "power_in"))
      (node (ref "U8") (pin "AC1") (pinfunction "VDD_AC1") (pintype "power_in"))
      (node (ref "U8") (pin "AG1") (pinfunction "VDD_AG1") (pintype "power_in"))
      (node (ref "U8") (pin "AJ31") (pinfunction "VDD_AJ31") (pintype "power_in"))
      (node (ref "U8") (pin "AL11") (pinfunction "VDD_AL11") (pintype "power_in"))
      (node (ref "U8") (pin "AL17") (pinfunction "VDD_AL17") (pintype "power_in"))
      (node (ref "U8") (pin "AL25") (pinfunction "VDD_AL25") (pintype "power_in"))
      (node (ref "U8") (pin "AL3") (pinfunction "VDD_AL3") (pintype "power_in"))
      (node (ref "U8") (pin "AL7") (pinfunction "VDD_AL7") (pintype "power_in"))
      (node (ref "U8") (pin "B28") (pinfunction "VDD_B28") (pintype "power_in"))
      (node (ref "U8") (pin "B8") (pinfunction "VDD_B8") (pintype "power_in"))
      (node (ref "U8") (pin "C1") (pinfunction "VDD_C1") (pintype "power_in"))
      (node (ref "U8") (pin "E1") (pinfunction "VDDH_E1") (pintype "power_in"))
      (node (ref "U8") (pin "E31") (pinfunction "VDD_E31") (pintype "power_in"))
      (node (ref "U8") (pin "L1") (pinfunction "VDD_L1") (pintype "power_in"))
      (node (ref "U8") (pin "N31") (pinfunction "VDD_N31") (pintype "power_in"))
      (node (ref "U8") (pin "U1") (pinfunction "VDD_U1") (pintype "power_in"))
      (node (ref "U9") (pin "1") (pinfunction "VCC(A)_1") (pintype "power_in"))
    )
    (net (code "80") (name "VDD_SWD0") (class "Default")
      (node (ref "C39") (pin "1") (pinfunction "1_1") (pintype "passive"))
      (node (ref "C41") (pin "1") (pinfunction "1_1") (pintype "passive"))
      (node (ref "J9") (pin "1") (pinfunction "VCC_1") (pintype "passive"))
      (node (ref "U10") (pin "8") (pinfunction "VCC(B)_8") (pintype "power_in"))
      (node (ref "U9") (pin "8") (pinfunction "VCC(B)_8") (pintype "power_in"))
    )
    (net (code "81") (name "unconnected-(J9-GND-Pad9)") (class "Default")
      (node (ref "J9") (pin "9") (pinfunction "GND_9") (pintype "passive+no_connect"))
    )
    (net (code "82") (name "unconnected-(J9-KEY-Pad7)") (class "Default")
      (node (ref "J9") (pin "7") (pinfunction "KEY_7") (pintype "passive+no_connect"))
    )
    (net (code "83") (name "unconnected-(J9-TDI-Pad8)") (class "Default")
      (node (ref "J9") (pin "8") (pinfunction "TDI_8") (pintype "passive+no_connect"))
    )
    (net (code "84") (name "unconnected-(J10-Pad6)") (class "Default")
      (node (ref "J10") (pin "6") (pintype "passive+no_connect"))
    )
    (net (code "85") (name "unconnected-(J10-Pad7)") (class "Default")
      (node (ref "J10") (pin "7") (pintype "passive+no_connect"))
    )
    (net (code "86") (name "unconnected-(J10-Pad8)") (class "Default")
      (node (ref "J10") (pin "8") (pintype "passive+no_connect"))
    )
    (net (code "87") (name "unconnected-(J10-Pad9)") (class "Default")
      (node (ref "J10") (pin "9") (pintype "passive"))
    )
    (net (code "88") (name "unconnected-(Q3B-D2-Pad3)") (class "Default")
      (node (ref "Q3") (pin "3") (pinfunction "D2_3") (pintype "passive+no_connect"))
    )
    (net (code "89") (name "unconnected-(Q3B-G2-Pad5)") (class "Default")
      (node (ref "Q3") (pin "5") (pinfunction "G2_5") (pintype "passive+no_connect"))
    )
    (net (code "90") (name "unconnected-(Q3B-S2-Pad4)") (class "Default")
      (node (ref "Q3") (pin "4") (pinfunction "S2_4") (pintype "passive+no_connect"))
    )
    (net (code "91") (name "unconnected-(U8A-DCC-PadA21)") (class "Default")
      (node (ref "U8") (pin "A21") (pinfunction "DCC_A21") (pintype "output+no_connect"))
    )
    (net (code "92") (name "unconnected-(U8A-DCCD-PadB10)") (class "Default")
      (node (ref "U8") (pin "B10") (pinfunction "DCCD_B10") (pintype "power_in+no_connect"))
    )
    (net (code "93") (name "unconnected-(U8A-DCCH-PadJ1)") (class "Default")
      (node (ref "U8") (pin "J1") (pinfunction "DCCH_J1") (pintype "power_in+no_connect"))
    )
    (net (code "94") (name "unconnected-(U8A-DECF-PadAG31)") (class "Default")
      (node (ref "U8") (pin "AG31") (pinfunction "DECF_AG31") (pintype "power_in+no_connect"))
    )
    (net (code "95") (name "unconnected-(U8B-N.C.-PadD2)") (class "Default")
      (node (ref "U8") (pin "D2") (pinfunction "N.C._D2") (pintype "passive+no_connect"))
    )
    (net (code "96") (name "unconnected-(U8B-N.C.-PadF2)") (class "Default")
      (node (ref "U8") (pin "F2") (pinfunction "N.C._F2") (pintype "passive+no_connect"))
    )
    (net (code "97") (name "unconnected-(U8B-N.C.-PadT2)") (class "Default")
      (node (ref "U8") (pin "T2") (pinfunction "N.C._T2") (pintype "passive+no_connect"))
    )
    (net (code "98") (name "unconnected-(U8C-P0.04{slash}AIN0-PadV2)") (class "Default")
      (node (ref "U8") (pin "V2") (pinfunction "P0.04/AIN0_V2") (pintype "bidirectional+no_connect"))
    )
    (net (code "99") (name "unconnected-(U8C-P0.05{slash}AIN1-PadY2)") (class "Default")
      (node (ref "U8") (pin "Y2") (pinfunction "P0.05/AIN1_Y2") (pintype "bidirectional+no_connect"))
    )
    (net (code "100") (name "unconnected-(U8C-P0.06{slash}AIN2-PadAB2)") (class "Default")
      (node (ref "U8") (pin "AB2") (pinfunction "P0.06/AIN2_AB2") (pintype "bidirectional+no_connect"))
    )
    (net (code "101") (name "unconnected-(U8C-P0.07{slash}AIN3-PadAD2)") (class "Default")
      (node (ref "U8") (pin "AD2") (pinfunction "P0.07/AIN3_AD2") (pintype "bidirectional+no_connect"))
    )
    (net (code "102") (name "unconnected-(U8C-P0.08{slash}TRACEDATA[3]-PadAH2)") (class "Default")
      (node (ref "U8") (pin "AH2") (pinfunction "P0.08/TRACEDATA[3]_AH2") (pintype "bidirectional+no_connect"))
    )
    (net (code "103") (name "unconnected-(U8C-P0.09{slash}TRACEDATA[2]-PadAJ1)") (class "Default")
      (node (ref "U8") (pin "AJ1") (pinfunction "P0.09/TRACEDATA[2]_AJ1") (pintype "bidirectional+no_connect"))
    )
    (net (code "104") (name "unconnected-(U8C-P0.10{slash}TRACEDATA[1]-PadAK2)") (class "Default")
      (node (ref "U8") (pin "AK2") (pinfunction "P0.10/TRACEDATA[1]_AK2") (pintype "bidirectional+no_connect"))
    )
    (net (code "105") (name "unconnected-(U8C-P0.11{slash}TRACEDATA[0]-PadAK4)") (class "Default")
      (node (ref "U8") (pin "AK4") (pinfunction "P0.11/TRACEDATA[0]_AK4") (pintype "bidirectional+no_connect"))
    )
    (net (code "106") (name "unconnected-(U8C-P0.12{slash}TRACECLK-PadAK6)") (class "Default")
      (node (ref "U8") (pin "AK6") (pinfunction "P0.12/TRACECLK_AK6") (pintype "bidirectional+no_connect"))
    )
    (net (code "107") (name "unconnected-(U8C-P0.14{slash}QSPI[1]-PadAK8)") (class "Default")
      (node (ref "U8") (pin "AK8") (pinfunction "P0.14/QSPI[1]_AK8") (pintype "bidirectional+no_connect"))
    )
    (net (code "108") (name "unconnected-(U8C-P0.15{slash}QSPI[2]-PadAK10)") (class "Default")
      (node (ref "U8") (pin "AK10") (pinfunction "P0.15/QSPI[2]_AK10") (pintype "bidirectional+no_connect"))
    )
    (net (code "109") (name "unconnected-(U8C-P0.17{slash}QSPI_CLK-PadAK12)") (class "Default")
      (node (ref "U8") (pin "AK12") (pinfunction "P0.17/QSPI_CLK_AK12") (pintype "bidirectional+no_connect"))
    )
    (net (code "110") (name "unconnected-(U8C-P0.18{slash}QSPI_CS-PadAK14)") (class "Default")
      (node (ref "U8") (pin "AK14") (pinfunction "P0.18/QSPI_CS_AK14") (pintype "bidirectional+no_connect"))
    )
    (net (code "111") (name "unconnected-(U8C-P0.20-PadAK16)") (class "Default")
      (node (ref "U8") (pin "AK16") (pinfunction "P0.20_AK16") (pintype "bidirectional+no_connect"))
    )
    (net (code "112") (name "unconnected-(U8C-P0.22-PadAK18)") (class "Default")
      (node (ref "U8") (pin "AK18") (pinfunction "P0.22_AK18") (pintype "bidirectional+no_connect"))
    )
    (net (code "113") (name "unconnected-(U8C-P0.23-PadAK20)") (class "Default")
      (node (ref "U8") (pin "AK20") (pinfunction "P0.23_AK20") (pintype "bidirectional+no_connect"))
    )
    (net (code "114") (name "unconnected-(U8C-P0.25{slash}AIN4-PadAK28)") (class "Default")
      (node (ref "U8") (pin "AK28") (pinfunction "P0.25/AIN4_AK28") (pintype "bidirectional+no_connect"))
    )
    (net (code "115") (name "unconnected-(U8C-P0.27{slash}AIN6-PadAK30)") (class "Default")
      (node (ref "U8") (pin "AK30") (pinfunction "P0.27/AIN6_AK30") (pintype "bidirectional+no_connect"))
    )
    (net (code "116") (name "unconnected-(U8C-P0.28{slash}AIN7-PadAE31)") (class "Default")
      (node (ref "U8") (pin "AE31") (pinfunction "P0.28/AIN7_AE31") (pintype "bidirectional+no_connect"))
    )
    (net (code "117") (name "unconnected-(U8D-P1.00-PadM2)") (class "Default")
      (node (ref "U8") (pin "M2") (pinfunction "P1.00_M2") (pintype "bidirectional+no_connect"))
    )
    (net (code "118") (name "unconnected-(U8D-P1.01-PadP2)") (class "Default")
      (node (ref "U8") (pin "P2") (pinfunction "P1.01_P2") (pintype "bidirectional+no_connect"))
    )
    (net (code "119") (name "unconnected-(U8D-P1.02{slash}I2C-PadAE1)") (class "Default")
      (node (ref "U8") (pin "AE1") (pinfunction "P1.02/I2C_AE1") (pintype "bidirectional+no_connect"))
    )
    (net (code "120") (name "unconnected-(U8D-P1.03{slash}I2C-PadAF2)") (class "Default")
      (node (ref "U8") (pin "AF2") (pinfunction "P1.03/I2C_AF2") (pintype "bidirectional+no_connect"))
    )
    (net (code "121") (name "unconnected-(U8D-P1.05-PadAK22)") (class "Default")
      (node (ref "U8") (pin "AK22") (pinfunction "P1.05_AK22") (pintype "bidirectional+no_connect"))
    )
    (net (code "122") (name "unconnected-(U8D-P1.07-PadAK24)") (class "Default")
      (node (ref "U8") (pin "AK24") (pinfunction "P1.07_AK24") (pintype "bidirectional+no_connect"))
    )
    (net (code "123") (name "unconnected-(U8D-P1.09-PadAK26)") (class "Default")
      (node (ref "U8") (pin "AK26") (pinfunction "P1.09_AK26") (pintype "bidirectional+no_connect"))
    )
    (net (code "124") (name "unconnected-(U8D-P1.10-PadR31)") (class "Default")
      (node (ref "U8") (pin "R31") (pinfunction "P1.10_R31") (pintype "bidirectional+no_connect"))
    )
    (net (code "125") (name "unconnected-(U8D-P1.13-PadA17)") (class "Default")
      (node (ref "U8") (pin "A17") (pinfunction "P1.13_A17") (pintype "bidirectional+no_connect"))
    )
    (net (code "126") (name "unconnected-(U8D-P1.15-PadB14)") (class "Default")
      (node (ref "U8") (pin "B14") (pinfunction "P1.15_B14") (pintype "bidirectional+no_connect"))
    )
  )
)
